# eng.net
KiCad netlist of a schematic drawn in EAGLE
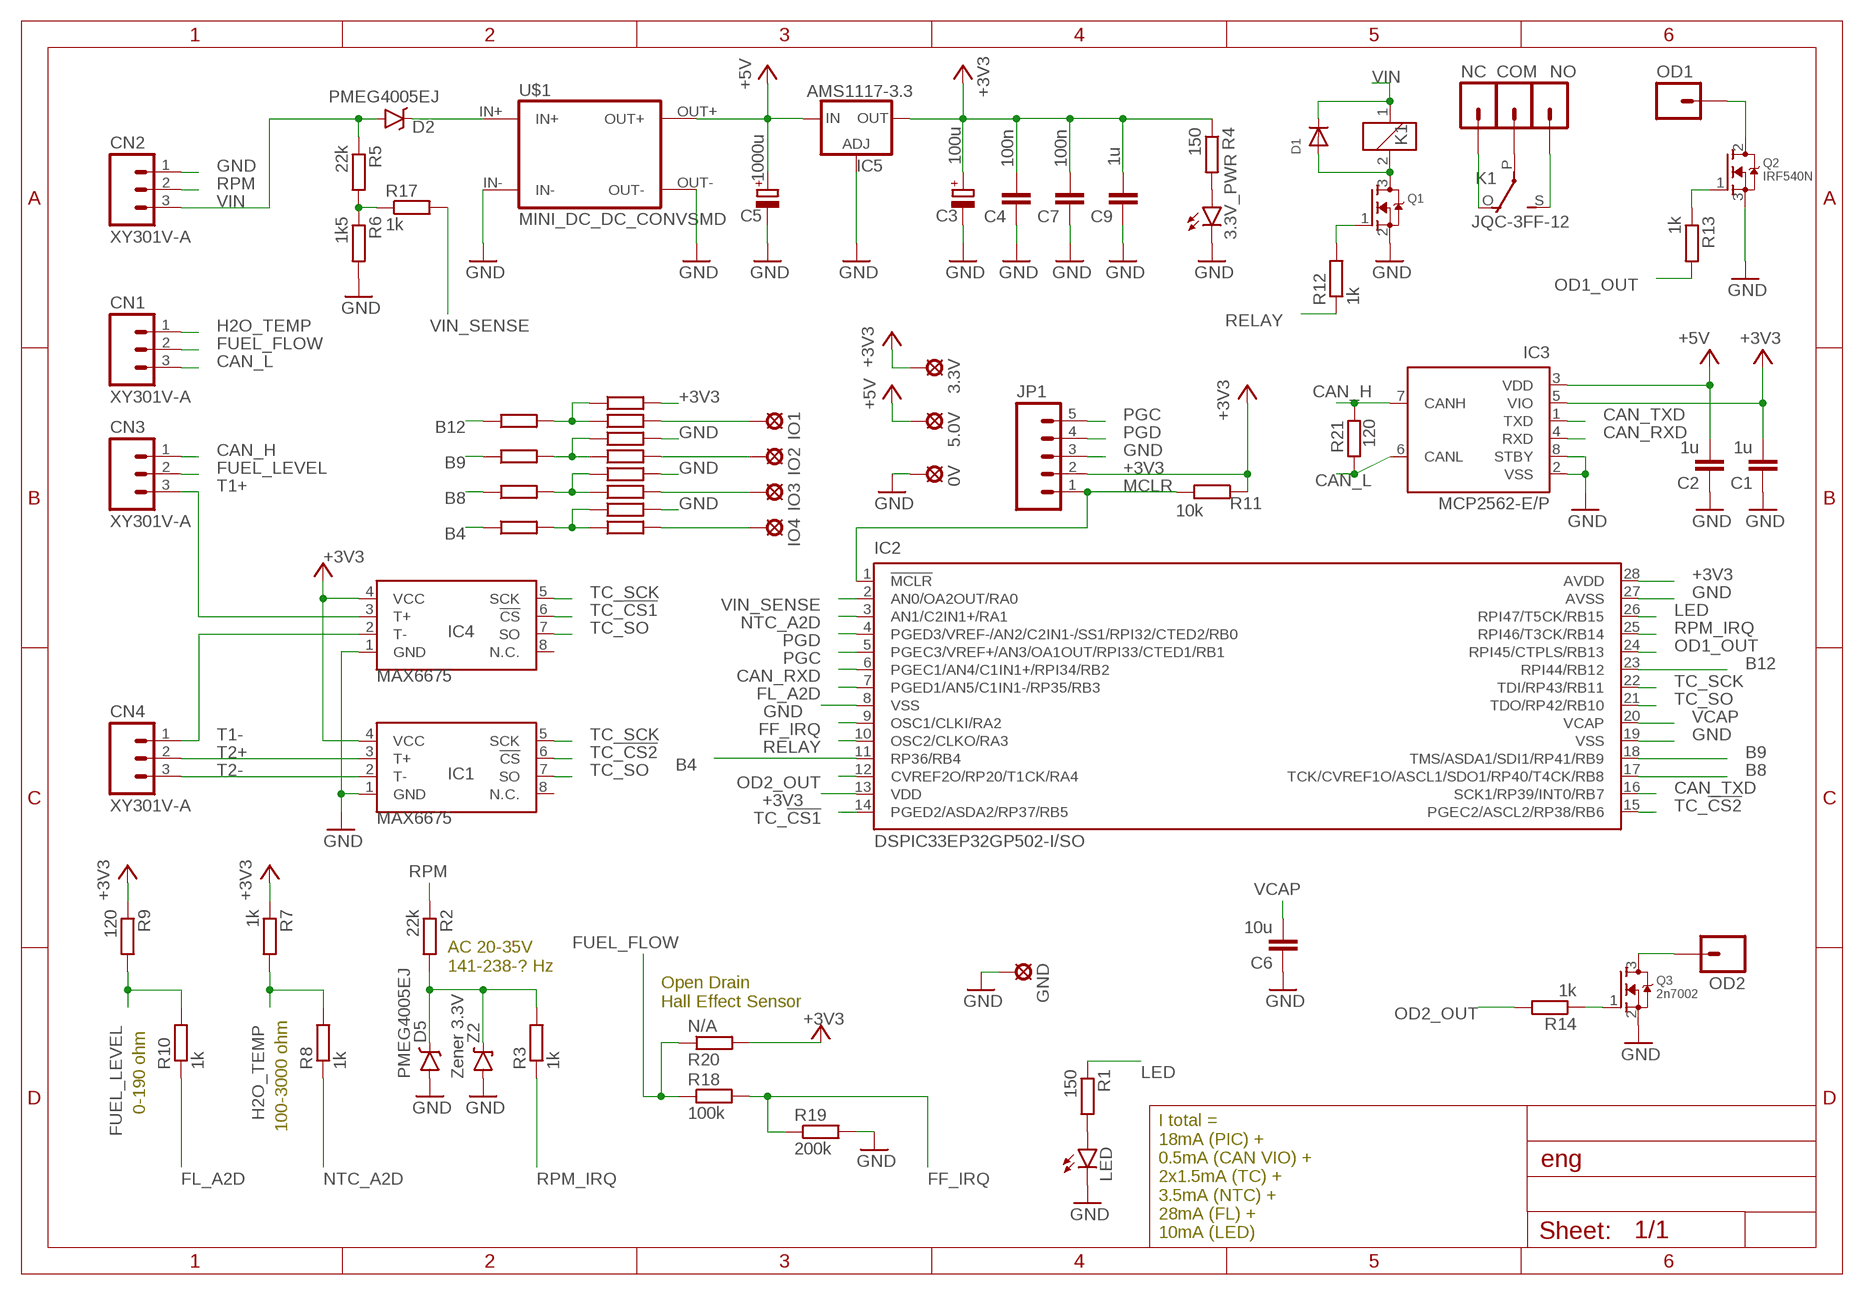
[diagram p0: schematic, sheet 1]

(export (version "E")
  (design (tool "Eeschema 10.0.6"))
  (components
    (comp (ref "0V")
      (value "LSP10")
      (footprint "eagle-import:LSP10")
      (libsource (lib "eagle-import") (part "LSP10"))
    )
    (comp (ref "3.3V")
      (value "LSP10")
      (footprint "eagle-import:LSP10")
      (libsource (lib "eagle-import") (part "LSP10"))
    )
    (comp (ref "3.3V_PWR")
      (value "LED-FKIT-1206")
      (footprint "eagle-import:FKIT-LED-1206")
      (libsource (lib "eagle-import") (part "LED-FKIT-1206"))
    )
    (comp (ref "5.0V")
      (value "LSP10")
      (footprint "eagle-import:LSP10")
      (libsource (lib "eagle-import") (part "LSP10"))
    )
    (comp (ref "C1")
      (value "1u")
      (footprint "eagle-import:C0603K")
      (libsource (lib "eagle-import") (part "C-EUC0603K"))
    )
    (comp (ref "C2")
      (value "1u")
      (footprint "eagle-import:C0603K")
      (libsource (lib "eagle-import") (part "C-EUC0603K"))
    )
    (comp (ref "C3")
      (value "100u")
      (footprint "eagle-import:E2,5-7")
      (libsource (lib "eagle-import") (part "CPOL-EUE2.5-7"))
    )
    (comp (ref "C4")
      (value "100n")
      (footprint "eagle-import:C0603K")
      (libsource (lib "eagle-import") (part "C-EUC0603K"))
    )
    (comp (ref "C5")
      (value "1000u")
      (footprint "eagle-import:E3,5-8")
      (libsource (lib "eagle-import") (part "CPOL-EUE3.5-8"))
    )
    (comp (ref "C6")
      (value "10u")
      (footprint "eagle-import:C3225")
      (libsource (lib "eagle-import") (part "C-EUC3225"))
    )
    (comp (ref "C7")
      (value "100n")
      (footprint "eagle-import:C0603K")
      (libsource (lib "eagle-import") (part "C-EUC0603K"))
    )
    (comp (ref "C9")
      (value "1u")
      (footprint "eagle-import:C0603")
      (libsource (lib "eagle-import") (part "C-EUC0603"))
    )
    (comp (ref "CN1")
      (value "XY301V-A")
      (footprint "eagle-import:XY301V-A")
      (libsource (lib "eagle-import") (part "XY301V-A"))
    )
    (comp (ref "CN2")
      (value "XY301V-A")
      (footprint "eagle-import:XY301V-A")
      (libsource (lib "eagle-import") (part "XY301V-A"))
    )
    (comp (ref "CN3")
      (value "XY301V-A")
      (footprint "eagle-import:XY301V-A")
      (libsource (lib "eagle-import") (part "XY301V-A"))
    )
    (comp (ref "CN4")
      (value "XY301V-A")
      (footprint "eagle-import:XY301V-A")
      (libsource (lib "eagle-import") (part "XY301V-A"))
    )
    (comp (ref "COM")
      (value "M01PTH_LONGPAD")
      (footprint "eagle-import:1X01_LONGPAD")
      (libsource (lib "eagle-import") (part "M01PTH_LONGPAD"))
    )
    (comp (ref "D1")
      (value "DIODESMA")
      (footprint "eagle-import:SMADIODE")
      (libsource (lib "eagle-import") (part "DIODESMA"))
    )
    (comp (ref "D2")
      (value "PMEG4005EJ")
      (footprint "eagle-import:SOD-323")
      (libsource (lib "eagle-import") (part "DIODE-SCHOTTKY-PMEG4005EJ"))
    )
    (comp (ref "D5")
      (value "PMEG4005EJ")
      (footprint "eagle-import:SOD-323")
      (libsource (lib "eagle-import") (part "DIODE-SCHOTTKY-PMEG4005EJ"))
    )
    (comp (ref "GND")
      (value "LSP10")
      (footprint "eagle-import:LSP10")
      (libsource (lib "eagle-import") (part "LSP10"))
    )
    (comp (ref "IC1")
      (value "MAX6675")
      (footprint "eagle-import:SO08")
      (libsource (lib "eagle-import") (part "MAX6675"))
    )
    (comp (ref "IC2")
      (value "DSPIC33EP32GP502-I/SO")
      (footprint "eagle-import:SO28W")
      (libsource (lib "eagle-import") (part "DSPIC33EP502?-I/SO32GP"))
    )
    (comp (ref "IC3")
      (value "MCP2562-E/P")
      (footprint "eagle-import:DIL8")
      (libsource (lib "eagle-import") (part "MCP2562-E/P"))
    )
    (comp (ref "IC4")
      (value "MAX6675")
      (footprint "eagle-import:SO08")
      (libsource (lib "eagle-import") (part "MAX6675"))
    )
    (comp (ref "IC5")
      (value "AMS1117-3.3")
      (footprint "eagle-import:SOT223")
      (libsource (lib "eagle-import") (part "LD117A?S33TR"))
    )
    (comp (ref "IO1")
      (value "LSP10")
      (footprint "eagle-import:LSP10")
      (libsource (lib "eagle-import") (part "LSP10"))
    )
    (comp (ref "IO2")
      (value "LSP10")
      (footprint "eagle-import:LSP10")
      (libsource (lib "eagle-import") (part "LSP10"))
    )
    (comp (ref "IO3")
      (value "LSP10")
      (footprint "eagle-import:LSP10")
      (libsource (lib "eagle-import") (part "LSP10"))
    )
    (comp (ref "IO4")
      (value "LSP10")
      (footprint "eagle-import:LSP10")
      (libsource (lib "eagle-import") (part "LSP10"))
    )
    (comp (ref "JP1")
      (value "M05PTH")
      (footprint "eagle-import:1X05")
      (libsource (lib "eagle-import") (part "M05PTH"))
    )
    (comp (ref "K1")
      (value "JQC-3FF-12")
      (footprint "eagle-import:G5LE")
      (libsource (lib "eagle-import") (part "G5L"))
    )
    (comp (ref "LED")
      (value "LED-FKIT-1206")
      (footprint "eagle-import:FKIT-LED-1206")
      (libsource (lib "eagle-import") (part "LED-FKIT-1206"))
    )
    (comp (ref "NC")
      (value "M01PTH_LONGPAD")
      (footprint "eagle-import:1X01_LONGPAD")
      (libsource (lib "eagle-import") (part "M01PTH_LONGPAD"))
    )
    (comp (ref "NO")
      (value "M01PTH_LONGPAD")
      (footprint "eagle-import:1X01_LONGPAD")
      (libsource (lib "eagle-import") (part "M01PTH_LONGPAD"))
    )
    (comp (ref "OD1")
      (value "M01PTH_LONGPAD")
      (footprint "eagle-import:1X01_LONGPAD")
      (libsource (lib "eagle-import") (part "M01PTH_LONGPAD"))
    )
    (comp (ref "OD2")
      (value "M01PTH_LONGPAD")
      (footprint "eagle-import:1X01_LONGPAD")
      (libsource (lib "eagle-import") (part "M01PTH_LONGPAD"))
    )
    (comp (ref "Q1")
      (value "MOSFET-NREFLOW")
      (footprint "eagle-import:SOT23")
      (libsource (lib "eagle-import") (part "MOSFET-NREFLOW"))
    )
    (comp (ref "Q2")
      (value "IRF540N")
      (footprint "eagle-import:TO220V")
      (libsource (lib "eagle-import") (part "MOSFET-NGDS_TO220V"))
    )
    (comp (ref "Q3")
      (value "2n7002")
      (footprint "eagle-import:SOT23")
      (libsource (lib "eagle-import") (part "MOSFET-NREFLOW"))
    )
    (comp (ref "R1")
      (value "150")
      (footprint "eagle-import:R0603")
      (libsource (lib "eagle-import") (part "R-EU_R0603"))
    )
    (comp (ref "R2")
      (value "22k")
      (footprint "eagle-import:R0603")
      (libsource (lib "eagle-import") (part "R-EU_R0603"))
    )
    (comp (ref "R3")
      (value "1k")
      (footprint "eagle-import:R0603")
      (libsource (lib "eagle-import") (part "R-EU_R0603"))
    )
    (comp (ref "R4")
      (value "150")
      (footprint "eagle-import:R0603")
      (libsource (lib "eagle-import") (part "R-EU_R0603"))
    )
    (comp (ref "R5")
      (value "22k")
      (footprint "eagle-import:R0603")
      (libsource (lib "eagle-import") (part "R-EU_R0603"))
    )
    (comp (ref "R6")
      (value "1k5")
      (footprint "eagle-import:R0603")
      (libsource (lib "eagle-import") (part "R-EU_R0603"))
    )
    (comp (ref "R7")
      (value "1k")
      (footprint "eagle-import:R0603")
      (libsource (lib "eagle-import") (part "R-EU_R0603"))
    )
    (comp (ref "R8")
      (value "1k")
      (footprint "eagle-import:R0603")
      (libsource (lib "eagle-import") (part "R-EU_R0603"))
    )
    (comp (ref "R9")
      (value "120")
      (footprint "eagle-import:R0603")
      (libsource (lib "eagle-import") (part "R-EU_R0603"))
    )
    (comp (ref "R10")
      (value "1k")
      (footprint "eagle-import:R0603")
      (libsource (lib "eagle-import") (part "R-EU_R0603"))
    )
    (comp (ref "R11")
      (value "10k")
      (footprint "eagle-import:R0603")
      (libsource (lib "eagle-import") (part "R-EU_R0603"))
    )
    (comp (ref "R12")
      (value "1k")
      (footprint "eagle-import:R0603")
      (libsource (lib "eagle-import") (part "R-EU_R0603"))
    )
    (comp (ref "R13")
      (value "1k")
      (footprint "eagle-import:R0603")
      (libsource (lib "eagle-import") (part "R-EU_R0603"))
    )
    (comp (ref "R14")
      (value "1k")
      (footprint "eagle-import:R0603")
      (libsource (lib "eagle-import") (part "R-EU_R0603"))
    )
    (comp (ref "R15")
      (value "N/A")
      (footprint "eagle-import:R0603")
      (libsource (lib "eagle-import") (part "R-EU_R0603"))
    )
    (comp (ref "R16")
      (value "N/A")
      (footprint "eagle-import:R0603")
      (libsource (lib "eagle-import") (part "R-EU_R0603"))
    )
    (comp (ref "R17")
      (value "1k")
      (footprint "eagle-import:R0603")
      (libsource (lib "eagle-import") (part "R-EU_R0603"))
    )
    (comp (ref "R18")
      (value "100k")
      (footprint "eagle-import:R0603")
      (libsource (lib "eagle-import") (part "R-EU_R0603"))
    )
    (comp (ref "R19")
      (value "200k")
      (footprint "eagle-import:R0603")
      (libsource (lib "eagle-import") (part "R-EU_R0603"))
    )
    (comp (ref "R20")
      (value "N/A")
      (footprint "eagle-import:R0603")
      (libsource (lib "eagle-import") (part "R-EU_R0603"))
    )
    (comp (ref "R21")
      (value "120")
      (footprint "eagle-import:R0603")
      (libsource (lib "eagle-import") (part "R-EU_R0603"))
    )
    (comp (ref "R23")
      (value "N/A")
      (footprint "eagle-import:R0603")
      (libsource (lib "eagle-import") (part "R-EU_R0603"))
    )
    (comp (ref "R24")
      (value "N/A")
      (footprint "eagle-import:R0603")
      (libsource (lib "eagle-import") (part "R-EU_R0603"))
    )
    (comp (ref "R25")
      (value "N/A")
      (footprint "eagle-import:R0603")
      (libsource (lib "eagle-import") (part "R-EU_R0603"))
    )
    (comp (ref "R26")
      (value "N/A")
      (footprint "eagle-import:R0603")
      (libsource (lib "eagle-import") (part "R-EU_R0603"))
    )
    (comp (ref "R29")
      (value "N/A")
      (footprint "eagle-import:R0603")
      (libsource (lib "eagle-import") (part "R-EU_R0603"))
    )
    (comp (ref "R30")
      (value "N/A")
      (footprint "eagle-import:R0603")
      (libsource (lib "eagle-import") (part "R-EU_R0603"))
    )
    (comp (ref "R31")
      (value "N/A")
      (footprint "eagle-import:R0603")
      (libsource (lib "eagle-import") (part "R-EU_R0603"))
    )
    (comp (ref "R32")
      (value "N/A")
      (footprint "eagle-import:R0603")
      (libsource (lib "eagle-import") (part "R-EU_R0603"))
    )
    (comp (ref "R35")
      (value "N/A")
      (footprint "eagle-import:R0603")
      (libsource (lib "eagle-import") (part "R-EU_R0603"))
    )
    (comp (ref "R36")
      (value "N/A")
      (footprint "eagle-import:R0603")
      (libsource (lib "eagle-import") (part "R-EU_R0603"))
    )
    (comp (ref "U$1")
      (value "MINI_DC_DC_CONVSMD")
      (footprint "eagle-import:DSN-MINI-360-SMD")
      (libsource (lib "eagle-import") (part "MINI_DC_DC_CONVSMD"))
    )
    (comp (ref "Z2")
      (value "Zener 3.3V")
      (footprint "eagle-import:MINIMELF")
      (libsource (lib "eagle-import") (part "DIODE-ZENERMM"))
    )
  )
  (nets
    (net (code "1") (name "+3V3") (class "Default")
      (node (ref "3.3V") (pin "MP") (pinfunction "MP_MP") (pintype "passive"))
      (node (ref "C1") (pin "2") (pinfunction "2_2") (pintype "passive"))
      (node (ref "C3") (pin "+") (pinfunction "+_+") (pintype "passive"))
      (node (ref "C4") (pin "2") (pinfunction "2_2") (pintype "passive"))
      (node (ref "C7") (pin "2") (pinfunction "2_2") (pintype "passive"))
      (node (ref "C9") (pin "2") (pinfunction "2_2") (pintype "passive"))
      (node (ref "IC1") (pin "4") (pinfunction "VCC_4") (pintype "power_in"))
      (node (ref "IC2") (pin "13") (pinfunction "VDD_13") (pintype "power_in"))
      (node (ref "IC2") (pin "28") (pinfunction "AVDD_28") (pintype "power_in"))
      (node (ref "IC3") (pin "5") (pinfunction "VIO_5") (pintype "power_in"))
      (node (ref "IC4") (pin "4") (pinfunction "VCC_4") (pintype "power_in"))
      (node (ref "IC5") (pin "2") (pinfunction "OUT_2") (pintype "passive"))
      (node (ref "IC5") (pin "@2") (pinfunction "OUT_@2") (pintype "passive"))
      (node (ref "JP1") (pin "2") (pinfunction "2_2") (pintype "passive"))
      (node (ref "R11") (pin "1") (pinfunction "1_1") (pintype "passive"))
      (node (ref "R20") (pin "2") (pinfunction "2_2") (pintype "passive"))
      (node (ref "R32") (pin "2") (pinfunction "2_2") (pintype "passive"))
      (node (ref "R4") (pin "1") (pinfunction "1_1") (pintype "passive"))
      (node (ref "R7") (pin "1") (pinfunction "1_1") (pintype "passive"))
      (node (ref "R9") (pin "1") (pinfunction "1_1") (pintype "passive"))
    )
    (net (code "2") (name "+5V") (class "Default")
      (node (ref "5.0V") (pin "MP") (pinfunction "MP_MP") (pintype "passive"))
      (node (ref "C2") (pin "2") (pinfunction "2_2") (pintype "passive"))
      (node (ref "C5") (pin "+") (pinfunction "+_+") (pintype "passive"))
      (node (ref "IC3") (pin "3") (pinfunction "VDD_3") (pintype "power_in"))
      (node (ref "IC5") (pin "3") (pinfunction "IN_3") (pintype "input"))
      (node (ref "U$1") (pin "OUT+") (pinfunction "OUT+_OUT+") (pintype "output"))
    )
    (net (code "3") (name "/B4") (class "Default")
      (node (ref "IC2") (pin "11") (pinfunction "RP36/RB4_11") (pintype "bidirectional"))
      (node (ref "R15") (pin "1") (pinfunction "1_1") (pintype "passive"))
    )
    (net (code "4") (name "/B8") (class "Default")
      (node (ref "IC2") (pin "17") (pinfunction "TCK/CVREF1O/ASCL1/SDO1/RP40/T4CK/RB8_17") (pintype "bidirectional"))
      (node (ref "R24") (pin "1") (pinfunction "1_1") (pintype "passive"))
    )
    (net (code "5") (name "/B9") (class "Default")
      (node (ref "IC2") (pin "18") (pinfunction "TMS/ASDA1/SDI1/RP41/RB9_18") (pintype "bidirectional"))
      (node (ref "R23") (pin "1") (pinfunction "1_1") (pintype "passive"))
    )
    (net (code "6") (name "/B12") (class "Default")
      (node (ref "IC2") (pin "23") (pinfunction "RPI44/RB12_23") (pintype "bidirectional"))
      (node (ref "R16") (pin "1") (pinfunction "1_1") (pintype "passive"))
    )
    (net (code "7") (name "/CAN_H") (class "Default")
      (node (ref "CN3") (pin "1") (pinfunction "1_1") (pintype "passive"))
      (node (ref "IC3") (pin "7") (pinfunction "CANH_7") (pintype "bidirectional"))
      (node (ref "R21") (pin "2") (pinfunction "2_2") (pintype "passive"))
    )
    (net (code "8") (name "/CAN_L") (class "Default")
      (node (ref "CN1") (pin "3") (pinfunction "3_3") (pintype "passive"))
      (node (ref "IC3") (pin "6") (pinfunction "CANL_6") (pintype "bidirectional"))
      (node (ref "R21") (pin "1") (pinfunction "1_1") (pintype "passive"))
    )
    (net (code "9") (name "/CAN_RXD") (class "Default")
      (node (ref "IC2") (pin "6") (pinfunction "PGEC1/AN4/C1IN1+/RPI34/RB2_6") (pintype "bidirectional"))
      (node (ref "IC3") (pin "4") (pinfunction "RXD_4") (pintype "output"))
    )
    (net (code "10") (name "/CAN_TXD") (class "Default")
      (node (ref "IC2") (pin "16") (pinfunction "SCK1/RP39/INT0/RB7_16") (pintype "bidirectional"))
      (node (ref "IC3") (pin "1") (pinfunction "TXD_1") (pintype "input"))
    )
    (net (code "11") (name "/FF_IRQ") (class "Default")
      (node (ref "IC2") (pin "9") (pinfunction "OSC1/CLKI/RA2_9") (pintype "input"))
      (node (ref "R18") (pin "2") (pinfunction "2_2") (pintype "passive"))
      (node (ref "R19") (pin "1") (pinfunction "1_1") (pintype "passive"))
    )
    (net (code "12") (name "/FL_A2D") (class "Default")
      (node (ref "IC2") (pin "7") (pinfunction "PGED1/AN5/C1IN1-/RP35/RB3_7") (pintype "bidirectional"))
      (node (ref "R10") (pin "1") (pinfunction "1_1") (pintype "passive"))
    )
    (net (code "13") (name "/FUEL_FLOW") (class "Default")
      (node (ref "CN1") (pin "2") (pinfunction "2_2") (pintype "passive"))
      (node (ref "R18") (pin "1") (pinfunction "1_1") (pintype "passive"))
      (node (ref "R20") (pin "1") (pinfunction "1_1") (pintype "passive"))
    )
    (net (code "14") (name "/FUEL_LEVEL") (class "Default")
      (node (ref "CN3") (pin "2") (pinfunction "2_2") (pintype "passive"))
      (node (ref "R10") (pin "2") (pinfunction "2_2") (pintype "passive"))
      (node (ref "R9") (pin "2") (pinfunction "2_2") (pintype "passive"))
    )
    (net (code "15") (name "/H2O_TEMP") (class "Default")
      (node (ref "CN1") (pin "1") (pinfunction "1_1") (pintype "passive"))
      (node (ref "R7") (pin "2") (pinfunction "2_2") (pintype "passive"))
      (node (ref "R8") (pin "2") (pinfunction "2_2") (pintype "passive"))
    )
    (net (code "16") (name "/LED") (class "Default")
      (node (ref "IC2") (pin "26") (pinfunction "RPI47/T5CK/RB15_26") (pintype "bidirectional"))
      (node (ref "R1") (pin "1") (pinfunction "1_1") (pintype "passive"))
    )
    (net (code "17") (name "/MCLR") (class "Default")
      (node (ref "IC2") (pin "1") (pinfunction "~{MCLR}_1") (pintype "input"))
      (node (ref "JP1") (pin "1") (pinfunction "1_1") (pintype "passive"))
      (node (ref "R11") (pin "2") (pinfunction "2_2") (pintype "passive"))
    )
    (net (code "18") (name "/NTC_A2D") (class "Default")
      (node (ref "IC2") (pin "3") (pinfunction "AN1/C2IN1+/RA1_3") (pintype "bidirectional"))
      (node (ref "R8") (pin "1") (pinfunction "1_1") (pintype "passive"))
    )
    (net (code "19") (name "/OD1_OUT") (class "Default")
      (node (ref "IC2") (pin "24") (pinfunction "RPI45/CTPLS/RB13_24") (pintype "bidirectional"))
      (node (ref "R13") (pin "2") (pinfunction "2_2") (pintype "passive"))
    )
    (net (code "20") (name "/OD2_OUT") (class "Default")
      (node (ref "IC2") (pin "12") (pinfunction "CVREF2O/RP20/T1CK/RA4_12") (pintype "bidirectional"))
      (node (ref "R14") (pin "2") (pinfunction "2_2") (pintype "passive"))
    )
    (net (code "21") (name "/PGC") (class "Default")
      (node (ref "IC2") (pin "5") (pinfunction "PGEC3/VREF+/AN3/OA1OUT/RPI33/CTED1/RB1_5") (pintype "bidirectional"))
      (node (ref "JP1") (pin "5") (pinfunction "5_5") (pintype "passive"))
    )
    (net (code "22") (name "/PGD") (class "Default")
      (node (ref "IC2") (pin "4") (pinfunction "PGED3/VREF-/AN2/C2IN1-/SS1/RPI32/CTED2/RB0_4") (pintype "bidirectional"))
      (node (ref "JP1") (pin "4") (pinfunction "4_4") (pintype "passive"))
    )
    (net (code "23") (name "/RELAY") (class "Default")
      (node (ref "IC2") (pin "10") (pinfunction "OSC2/CLKO/RA3_10") (pintype "bidirectional"))
      (node (ref "R12") (pin "1") (pinfunction "1_1") (pintype "passive"))
    )
    (net (code "24") (name "/RPM") (class "Default")
      (node (ref "CN2") (pin "2") (pinfunction "2_2") (pintype "passive"))
      (node (ref "R2") (pin "1") (pinfunction "1_1") (pintype "passive"))
    )
    (net (code "25") (name "/RPM_IRQ") (class "Default")
      (node (ref "IC2") (pin "25") (pinfunction "RPI46/T3CK/RB14_25") (pintype "bidirectional"))
      (node (ref "R3") (pin "1") (pinfunction "1_1") (pintype "passive"))
    )
    (net (code "26") (name "/T1+") (class "Default")
      (node (ref "CN3") (pin "3") (pinfunction "3_3") (pintype "passive"))
      (node (ref "IC4") (pin "3") (pinfunction "T+_3") (pintype "input"))
    )
    (net (code "27") (name "/T1-") (class "Default")
      (node (ref "CN4") (pin "1") (pinfunction "1_1") (pintype "passive"))
      (node (ref "IC4") (pin "2") (pinfunction "T-_2") (pintype "input"))
    )
    (net (code "28") (name "/T2+") (class "Default")
      (node (ref "CN4") (pin "2") (pinfunction "2_2") (pintype "passive"))
      (node (ref "IC1") (pin "3") (pinfunction "T+_3") (pintype "input"))
    )
    (net (code "29") (name "/T2-") (class "Default")
      (node (ref "CN4") (pin "3") (pinfunction "3_3") (pintype "passive"))
      (node (ref "IC1") (pin "2") (pinfunction "T-_2") (pintype "input"))
    )
    (net (code "30") (name "/TC_SCK") (class "Default")
      (node (ref "IC1") (pin "5") (pinfunction "SCK_5") (pintype "input"))
      (node (ref "IC2") (pin "22") (pinfunction "TDI/RP43/RB11_22") (pintype "bidirectional"))
      (node (ref "IC4") (pin "5") (pinfunction "SCK_5") (pintype "input"))
    )
    (net (code "31") (name "/TC_SO") (class "Default")
      (node (ref "IC1") (pin "7") (pinfunction "SO_7") (pintype "output"))
      (node (ref "IC2") (pin "21") (pinfunction "TDO/RP42/RB10_21") (pintype "bidirectional"))
      (node (ref "IC4") (pin "7") (pinfunction "SO_7") (pintype "output"))
    )
    (net (code "32") (name "/TC_~{CS1}") (class "Default")
      (node (ref "IC2") (pin "14") (pinfunction "PGED2/ASDA2/RP37/RB5_14") (pintype "bidirectional"))
      (node (ref "IC4") (pin "6") (pinfunction "~{CS}_6") (pintype "input"))
    )
    (net (code "33") (name "/TC_~{CS2}") (class "Default")
      (node (ref "IC1") (pin "6") (pinfunction "~{CS}_6") (pintype "input"))
      (node (ref "IC2") (pin "15") (pinfunction "PGEC2/ASCL2/RP38/RB6_15") (pintype "bidirectional"))
    )
    (net (code "34") (name "/VCAP") (class "Default")
      (node (ref "C6") (pin "2") (pinfunction "2_2") (pintype "passive"))
      (node (ref "IC2") (pin "20") (pinfunction "VCAP_20") (pintype "power_in"))
    )
    (net (code "35") (name "/VIN") (class "Default")
      (node (ref "CN2") (pin "3") (pinfunction "3_3") (pintype "passive"))
      (node (ref "D1") (pin "C") (pinfunction "C_C") (pintype "passive"))
      (node (ref "D2") (pin "A") (pinfunction "A_A") (pintype "passive"))
      (node (ref "K1") (pin "1") (pinfunction "1_1") (pintype "passive"))
      (node (ref "R5") (pin "1") (pinfunction "1_1") (pintype "passive"))
    )
    (net (code "36") (name "/VIN_SENSE") (class "Default")
      (node (ref "IC2") (pin "2") (pinfunction "AN0/OA2OUT/RA0_2") (pintype "bidirectional"))
      (node (ref "R17") (pin "2") (pinfunction "2_2") (pintype "passive"))
    )
    (net (code "37") (name "GND") (class "Default")
      (node (ref "0V") (pin "MP") (pinfunction "MP_MP") (pintype "passive"))
      (node (ref "3.3V_PWR") (pin "C") (pinfunction "C_C") (pintype "passive"))
      (node (ref "C1") (pin "1") (pinfunction "1_1") (pintype "passive"))
      (node (ref "C2") (pin "1") (pinfunction "1_1") (pintype "passive"))
      (node (ref "C3") (pin "-") (pinfunction "-_-") (pintype "passive"))
      (node (ref "C4") (pin "1") (pinfunction "1_1") (pintype "passive"))
      (node (ref "C5") (pin "-") (pinfunction "-_-") (pintype "passive"))
      (node (ref "C6") (pin "1") (pinfunction "1_1") (pintype "passive"))
      (node (ref "C7") (pin "1") (pinfunction "1_1") (pintype "passive"))
      (node (ref "C9") (pin "1") (pinfunction "1_1") (pintype "passive"))
      (node (ref "CN2") (pin "1") (pinfunction "1_1") (pintype "passive"))
      (node (ref "D5") (pin "A") (pinfunction "A_A") (pintype "passive"))
      (node (ref "GND") (pin "MP") (pinfunction "MP_MP") (pintype "passive"))
      (node (ref "IC1") (pin "1") (pinfunction "GND_1") (pintype "power_in"))
      (node (ref "IC2") (pin "19") (pinfunction "VSS_19") (pintype "power_in"))
      (node (ref "IC2") (pin "27") (pinfunction "AVSS_27") (pintype "power_in"))
      (node (ref "IC2") (pin "8") (pinfunction "VSS_8") (pintype "power_in"))
      (node (ref "IC3") (pin "2") (pinfunction "VSS_2") (pintype "power_in"))
      (node (ref "IC3") (pin "8") (pinfunction "STBY_8") (pintype "input"))
      (node (ref "IC4") (pin "1") (pinfunction "GND_1") (pintype "power_in"))
      (node (ref "IC5") (pin "1") (pinfunction "ADJ_1") (pintype "input"))
      (node (ref "JP1") (pin "3") (pinfunction "3_3") (pintype "passive"))
      (node (ref "LED") (pin "C") (pinfunction "C_C") (pintype "passive"))
      (node (ref "Q1") (pin "2") (pinfunction "S_2") (pintype "bidirectional"))
      (node (ref "Q2") (pin "3") (pinfunction "S_3") (pintype "bidirectional"))
      (node (ref "Q3") (pin "2") (pinfunction "S_2") (pintype "bidirectional"))
      (node (ref "R19") (pin "2") (pinfunction "2_2") (pintype "passive"))
      (node (ref "R31") (pin "2") (pinfunction "2_2") (pintype "passive"))
      (node (ref "R35") (pin "2") (pinfunction "2_2") (pintype "passive"))
      (node (ref "R36") (pin "2") (pinfunction "2_2") (pintype "passive"))
      (node (ref "R6") (pin "2") (pinfunction "2_2") (pintype "passive"))
      (node (ref "U$1") (pin "IN-") (pinfunction "IN-_IN-") (pintype "power_in"))
      (node (ref "U$1") (pin "OUT-") (pinfunction "OUT-_OUT-") (pintype "power_in"))
      (node (ref "Z2") (pin "A") (pinfunction "A_A") (pintype "passive"))
    )
    (net (code "38") (name "Net-(3.3V_PWR-PadA)") (class "Default")
      (node (ref "3.3V_PWR") (pin "A") (pinfunction "A_A") (pintype "passive"))
      (node (ref "R4") (pin "2") (pinfunction "2_2") (pintype "passive"))
    )
    (net (code "39") (name "Net-(COM-Pad1)") (class "Default")
      (node (ref "COM") (pin "1") (pinfunction "1_1") (pintype "passive"))
      (node (ref "K1") (pin "P") (pinfunction "P_P") (pintype "passive"))
    )
    (net (code "40") (name "Net-(D2-PadC)") (class "Default")
      (node (ref "D2") (pin "C") (pinfunction "C_C") (pintype "passive"))
      (node (ref "U$1") (pin "IN+") (pinfunction "IN+_IN+") (pintype "input"))
    )
    (net (code "41") (name "Net-(D5-PadC)") (class "Default")
      (node (ref "D5") (pin "C") (pinfunction "C_C") (pintype "passive"))
      (node (ref "R2") (pin "2") (pinfunction "2_2") (pintype "passive"))
      (node (ref "R3") (pin "2") (pinfunction "2_2") (pintype "passive"))
      (node (ref "Z2") (pin "C") (pinfunction "C_C") (pintype "passive"))
    )
    (net (code "42") (name "Net-(IO1-PadMP)") (class "Default")
      (node (ref "IO1") (pin "MP") (pinfunction "MP_MP") (pintype "passive"))
      (node (ref "R26") (pin "2") (pinfunction "2_2") (pintype "passive"))
    )
    (net (code "43") (name "Net-(IO2-PadMP)") (class "Default")
      (node (ref "IO2") (pin "MP") (pinfunction "MP_MP") (pintype "passive"))
      (node (ref "R29") (pin "2") (pinfunction "2_2") (pintype "passive"))
    )
    (net (code "44") (name "Net-(IO3-PadMP)") (class "Default")
      (node (ref "IO3") (pin "MP") (pinfunction "MP_MP") (pintype "passive"))
      (node (ref "R30") (pin "2") (pinfunction "2_2") (pintype "passive"))
    )
    (net (code "45") (name "Net-(IO4-PadMP)") (class "Default")
      (node (ref "IO4") (pin "MP") (pinfunction "MP_MP") (pintype "passive"))
      (node (ref "R25") (pin "2") (pinfunction "2_2") (pintype "passive"))
    )
    (net (code "46") (name "Net-(K1-PadO)") (class "Default")
      (node (ref "K1") (pin "O") (pinfunction "O_O") (pintype "passive"))
      (node (ref "NC") (pin "1") (pinfunction "1_1") (pintype "passive"))
    )
    (net (code "47") (name "Net-(K1-PadS)") (class "Default")
      (node (ref "K1") (pin "S") (pinfunction "S_S") (pintype "passive"))
      (node (ref "NO") (pin "1") (pinfunction "1_1") (pintype "passive"))
    )
    (net (code "48") (name "Net-(LED-PadA)") (class "Default")
      (node (ref "LED") (pin "A") (pinfunction "A_A") (pintype "passive"))
      (node (ref "R1") (pin "2") (pinfunction "2_2") (pintype "passive"))
    )
    (net (code "49") (name "Net-(Q1-D)") (class "Default")
      (node (ref "D1") (pin "A") (pinfunction "A_A") (pintype "passive"))
      (node (ref "K1") (pin "2") (pinfunction "2_2") (pintype "passive"))
      (node (ref "Q1") (pin "3") (pinfunction "D_3") (pintype "bidirectional"))
    )
    (net (code "50") (name "Net-(Q1-G)") (class "Default")
      (node (ref "Q1") (pin "1") (pinfunction "G_1") (pintype "bidirectional"))
      (node (ref "R12") (pin "2") (pinfunction "2_2") (pintype "passive"))
    )
    (net (code "51") (name "Net-(Q2-D)") (class "Default")
      (node (ref "OD1") (pin "1") (pinfunction "1_1") (pintype "passive"))
      (node (ref "Q2") (pin "2") (pinfunction "D_2") (pintype "bidirectional"))
    )
    (net (code "52") (name "Net-(Q2-G)") (class "Default")
      (node (ref "Q2") (pin "1") (pinfunction "G_1") (pintype "bidirectional"))
      (node (ref "R13") (pin "1") (pinfunction "1_1") (pintype "passive"))
    )
    (net (code "53") (name "Net-(Q3-D)") (class "Default")
      (node (ref "OD2") (pin "1") (pinfunction "1_1") (pintype "passive"))
      (node (ref "Q3") (pin "3") (pinfunction "D_3") (pintype "bidirectional"))
    )
    (net (code "54") (name "Net-(Q3-G)") (class "Default")
      (node (ref "Q3") (pin "1") (pinfunction "G_1") (pintype "bidirectional"))
      (node (ref "R14") (pin "1") (pinfunction "1_1") (pintype "passive"))
    )
    (net (code "55") (name "Net-(R15-Pad2)") (class "Default")
      (node (ref "R15") (pin "2") (pinfunction "2_2") (pintype "passive"))
      (node (ref "R25") (pin "1") (pinfunction "1_1") (pintype "passive"))
      (node (ref "R31") (pin "1") (pinfunction "1_1") (pintype "passive"))
    )
    (net (code "56") (name "Net-(R16-Pad2)") (class "Default")
      (node (ref "R16") (pin "2") (pinfunction "2_2") (pintype "passive"))
      (node (ref "R26") (pin "1") (pinfunction "1_1") (pintype "passive"))
      (node (ref "R32") (pin "1") (pinfunction "1_1") (pintype "passive"))
    )
    (net (code "57") (name "Net-(R17-Pad1)") (class "Default")
      (node (ref "R17") (pin "1") (pinfunction "1_1") (pintype "passive"))
      (node (ref "R5") (pin "2") (pinfunction "2_2") (pintype "passive"))
      (node (ref "R6") (pin "1") (pinfunction "1_1") (pintype "passive"))
    )
    (net (code "58") (name "Net-(R23-Pad2)") (class "Default")
      (node (ref "R23") (pin "2") (pinfunction "2_2") (pintype "passive"))
      (node (ref "R29") (pin "1") (pinfunction "1_1") (pintype "passive"))
      (node (ref "R35") (pin "1") (pinfunction "1_1") (pintype "passive"))
    )
    (net (code "59") (name "Net-(R24-Pad2)") (class "Default")
      (node (ref "R24") (pin "2") (pinfunction "2_2") (pintype "passive"))
      (node (ref "R30") (pin "1") (pinfunction "1_1") (pintype "passive"))
      (node (ref "R36") (pin "1") (pinfunction "1_1") (pintype "passive"))
    )
    (net (code "60") (name "unconnected-(IC1-N.C.-Pad8)") (class "Default")
      (node (ref "IC1") (pin "8") (pinfunction "N.C._8") (pintype "no_connect"))
    )
    (net (code "61") (name "unconnected-(IC4-N.C.-Pad8)") (class "Default")
      (node (ref "IC4") (pin "8") (pinfunction "N.C._8") (pintype "no_connect"))
    )
  )
)
